# MAGI_sDIPBoard.net
KiCad netlist of a schematic drawn in Altium Designer
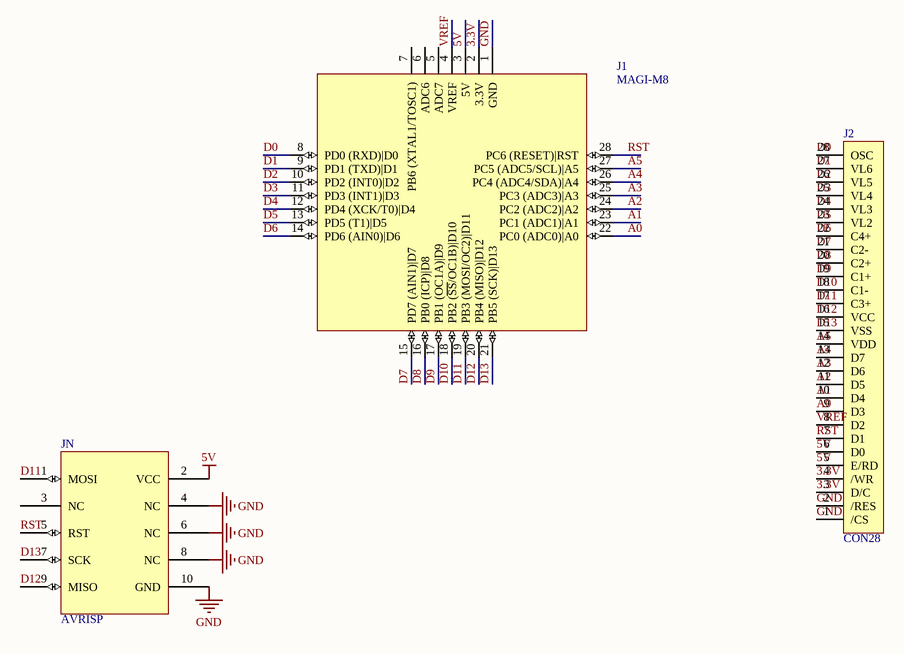
[diagram p0: MAGI'sDIPBoard.SchDoc]

(export (version "E")
  (design (tool "Eeschema 10.0.6"))
  (components
    (comp (ref "J1") (value "MAGI-M8") (footprint "MAGI-M8") (libsource (lib "MAGI-M8") (part "MAGI-M8")))
    (comp (ref "J2")
      (value "CON28")
      (footprint "28P3")
      (description "Connector")
      (libsource (lib "CON系列") (part "CON28"))
    )
    (comp (ref "JN") (value "AVRISP") (footprint "AVRISP") (libsource (lib "AVRISP") (part "AVRISP")))
  )
  (nets
    (net (code "1") (name "/3.3V") (class "Default")
      (node (ref "J1") (pin "2") (pinfunction "3.3V_2") (pintype "power_in"))
      (node (ref "J2") (pin "3") (pinfunction "D/C_3") (pintype "passive"))
      (node (ref "J2") (pin "4") (pinfunction "/WR_4") (pintype "passive"))
    )
    (net (code "2") (name "/A0") (class "Default")
      (node (ref "J1") (pin "22") (pinfunction "PC0_(ADC0)A0_22") (pintype "bidirectional"))
      (node (ref "J2") (pin "9") (pinfunction "D3_9") (pintype "passive"))
    )
    (net (code "3") (name "/A1") (class "Default")
      (node (ref "J1") (pin "23") (pinfunction "PC1_(ADC1)A1_23") (pintype "bidirectional"))
      (node (ref "J2") (pin "10") (pinfunction "D4_10") (pintype "passive"))
    )
    (net (code "4") (name "/A2") (class "Default")
      (node (ref "J1") (pin "24") (pinfunction "PC2_(ADC2)A2_24") (pintype "bidirectional"))
      (node (ref "J2") (pin "11") (pinfunction "D5_11") (pintype "passive"))
    )
    (net (code "5") (name "/A3") (class "Default")
      (node (ref "J1") (pin "25") (pinfunction "PC3_(ADC3)A3_25") (pintype "bidirectional"))
      (node (ref "J2") (pin "12") (pinfunction "D6_12") (pintype "passive"))
    )
    (net (code "6") (name "/A4") (class "Default")
      (node (ref "J1") (pin "26") (pinfunction "PC4_(ADC4/SDA)A4_26") (pintype "bidirectional"))
      (node (ref "J2") (pin "13") (pinfunction "D7_13") (pintype "passive"))
    )
    (net (code "7") (name "/A5") (class "Default")
      (node (ref "J1") (pin "27") (pinfunction "PC5_(ADC5/SCL)A5_27") (pintype "bidirectional"))
      (node (ref "J2") (pin "14") (pinfunction "VDD_14") (pintype "passive"))
    )
    (net (code "8") (name "/D0") (class "Default")
      (node (ref "J1") (pin "8") (pinfunction "PD0_(RXD)D0_8") (pintype "bidirectional"))
      (node (ref "J2") (pin "28") (pinfunction "OSC_28") (pintype "passive"))
    )
    (net (code "9") (name "/D1") (class "Default")
      (node (ref "J1") (pin "9") (pinfunction "PD1_(TXD)D1_9") (pintype "bidirectional"))
      (node (ref "J2") (pin "27") (pinfunction "VL6_27") (pintype "passive"))
    )
    (net (code "10") (name "/D2") (class "Default")
      (node (ref "J1") (pin "10") (pinfunction "PD2_(INT0)D2_10") (pintype "bidirectional"))
      (node (ref "J2") (pin "26") (pinfunction "VL5_26") (pintype "passive"))
    )
    (net (code "11") (name "/D3") (class "Default")
      (node (ref "J1") (pin "11") (pinfunction "PD3_(INT1)D3_11") (pintype "bidirectional"))
      (node (ref "J2") (pin "25") (pinfunction "VL4_25") (pintype "passive"))
    )
    (net (code "12") (name "/D4") (class "Default")
      (node (ref "J1") (pin "12") (pinfunction "PD4_(XCK/T0)D4_12") (pintype "bidirectional"))
      (node (ref "J2") (pin "24") (pinfunction "VL3_24") (pintype "passive"))
    )
    (net (code "13") (name "/D5") (class "Default")
      (node (ref "J1") (pin "13") (pinfunction "PD5_(T1)D5_13") (pintype "bidirectional"))
      (node (ref "J2") (pin "23") (pinfunction "VL2_23") (pintype "passive"))
    )
    (net (code "14") (name "/D6") (class "Default")
      (node (ref "J1") (pin "14") (pinfunction "PD6_(AIN0)D6_14") (pintype "bidirectional"))
      (node (ref "J2") (pin "22") (pinfunction "C4+_22") (pintype "passive"))
    )
    (net (code "15") (name "/D7") (class "Default")
      (node (ref "J1") (pin "15") (pinfunction "PD7_(AIN1)D7_15") (pintype "bidirectional"))
      (node (ref "J2") (pin "21") (pinfunction "C2-_21") (pintype "passive"))
    )
    (net (code "16") (name "/D8") (class "Default")
      (node (ref "J1") (pin "16") (pinfunction "PB0_(ICP)D8_16") (pintype "bidirectional"))
      (node (ref "J2") (pin "20") (pinfunction "C2+_20") (pintype "passive"))
    )
    (net (code "17") (name "/D9") (class "Default")
      (node (ref "J1") (pin "17") (pinfunction "PB1_(OC1A)D9_17") (pintype "bidirectional"))
      (node (ref "J2") (pin "19") (pinfunction "C1+_19") (pintype "passive"))
    )
    (net (code "18") (name "/D10") (class "Default")
      (node (ref "J1") (pin "18") (pinfunction "PB2_(~{SS}/OC1B)D10_18") (pintype "bidirectional"))
      (node (ref "J2") (pin "18") (pinfunction "C1-_18") (pintype "passive"))
    )
    (net (code "19") (name "/D11") (class "Default")
      (node (ref "J1") (pin "19") (pinfunction "PB3_(MOSI/OC2)D11_19") (pintype "bidirectional"))
      (node (ref "J2") (pin "17") (pinfunction "C3+_17") (pintype "passive"))
      (node (ref "JN") (pin "1") (pinfunction "MOSI_1") (pintype "bidirectional"))
    )
    (net (code "20") (name "/D12") (class "Default")
      (node (ref "J1") (pin "20") (pinfunction "PB4_(MISO)D12_20") (pintype "bidirectional"))
      (node (ref "J2") (pin "16") (pinfunction "VCC_16") (pintype "passive"))
      (node (ref "JN") (pin "9") (pinfunction "MISO_9") (pintype "bidirectional"))
    )
    (net (code "21") (name "/D13") (class "Default")
      (node (ref "J1") (pin "21") (pinfunction "PB5_(SCK)D13_21") (pintype "bidirectional"))
      (node (ref "J2") (pin "15") (pinfunction "VSS_15") (pintype "passive"))
      (node (ref "JN") (pin "7") (pinfunction "SCK_7") (pintype "bidirectional"))
    )
    (net (code "22") (name "/RST") (class "Default")
      (node (ref "J1") (pin "28") (pinfunction "PC6_(RESET)RST_28") (pintype "bidirectional"))
      (node (ref "J2") (pin "7") (pinfunction "D1_7") (pintype "passive"))
      (node (ref "JN") (pin "5") (pinfunction "RST_5") (pintype "bidirectional"))
    )
    (net (code "23") (name "/VREF") (class "Default")
      (node (ref "J1") (pin "4") (pinfunction "VREF_4") (pintype "passive"))
      (node (ref "J2") (pin "8") (pinfunction "D2_8") (pintype "passive"))
    )
    (net (code "24") (name "5V") (class "Default")
      (node (ref "J1") (pin "3") (pinfunction "5V_3") (pintype "power_in"))
      (node (ref "J2") (pin "5") (pinfunction "E/RD_5") (pintype "passive"))
      (node (ref "J2") (pin "6") (pinfunction "D0_6") (pintype "passive"))
      (node (ref "JN") (pin "2") (pinfunction "VCC_2") (pintype "power_in"))
    )
    (net (code "25") (name "GND") (class "Default")
      (node (ref "J1") (pin "1") (pinfunction "GND_1") (pintype "power_in"))
      (node (ref "J2") (pin "1") (pinfunction "/CS_1") (pintype "passive"))
      (node (ref "J2") (pin "2") (pinfunction "/RES_2") (pintype "passive"))
      (node (ref "JN") (pin "10") (pinfunction "GND_10") (pintype "power_in"))
      (node (ref "JN") (pin "4") (pinfunction "NC_4") (pintype "power_in"))
      (node (ref "JN") (pin "6") (pinfunction "NC_6") (pintype "power_in"))
      (node (ref "JN") (pin "8") (pinfunction "NC_8") (pintype "power_in"))
    )
    (net (code "26") (name "unconnected-(J1-ADC6-Pad6)") (class "Default")
      (node (ref "J1") (pin "6") (pinfunction "ADC6_6") (pintype "passive"))
    )
    (net (code "27") (name "unconnected-(J1-ADC7-Pad5)") (class "Default")
      (node (ref "J1") (pin "5") (pinfunction "ADC7_5") (pintype "passive"))
    )
    (net (code "28") (name "unconnected-(J1-PB6_(XTAL1{slash}TOSC1)-Pad7)") (class "Default")
      (node (ref "J1") (pin "7") (pinfunction "PB6_(XTAL1/TOSC1)_7") (pintype "passive"))
    )
    (net (code "29") (name "unconnected-(JN-NC-Pad3)") (class "Default")
      (node (ref "JN") (pin "3") (pinfunction "NC_3") (pintype "power_in"))
    )
  )
)
